# interface.net
KiCad netlist of a schematic drawn in Altium Designer
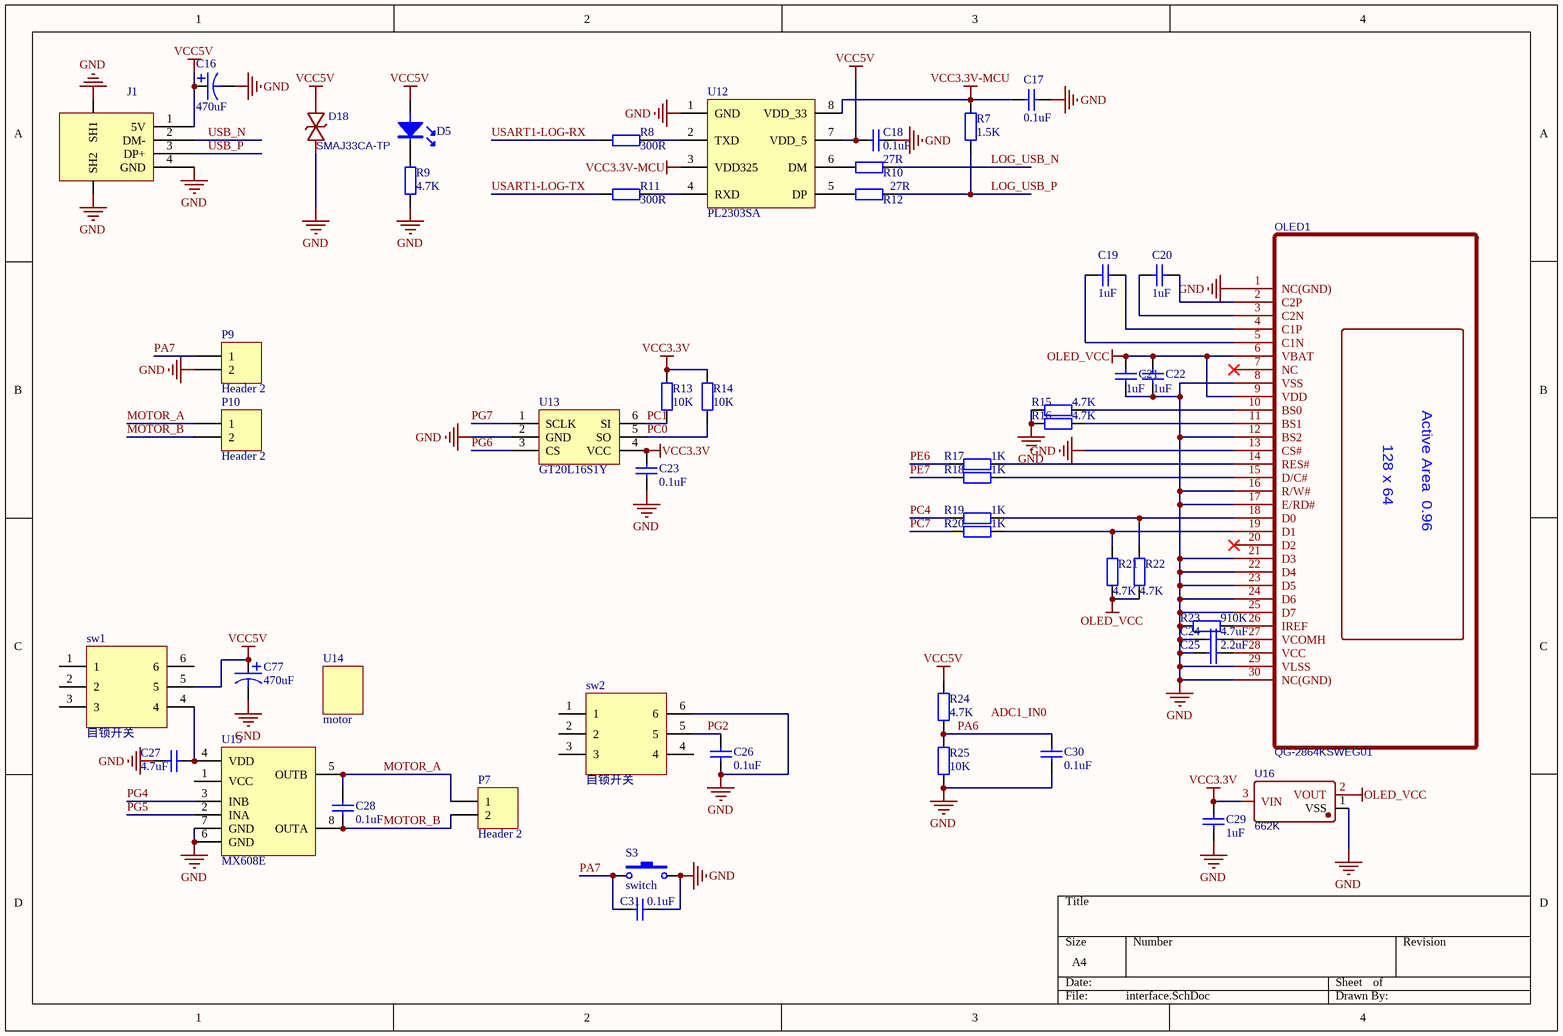
[diagram p0: interface.SchDoc]

(export (version "E")
  (design (tool "Eeschema 10.0.6"))
  (components
    (comp (ref "C16")
      (value "470uF")
      (footprint "CAP-SMD_BD10.0-L10.3-W10.3-FD")
      (description "贴片电容，1206")
      (libsource (lib "stm8l052r8t6开发板") (part "CAPACITOR"))
    )
    (comp (ref "C17")
      (value "0.1uF")
      (footprint "0603_C")
      (description "贴片电容，0603")
      (libsource (lib "extendBoard") (part "Cap"))
    )
    (comp (ref "C18")
      (value "0.1uF")
      (footprint "0603_C")
      (description "贴片电容，0603")
      (libsource (lib "extendBoard") (part "Cap"))
    )
    (comp (ref "C19")
      (value "1uF")
      (footprint "0603_C")
      (description "贴片电容，0603")
      (libsource (lib "stm8l052r8t6开发板") (part "Cap"))
    )
    (comp (ref "C20")
      (value "1uF")
      (footprint "0603_C")
      (description "贴片电容，0603")
      (libsource (lib "stm8l052r8t6开发板") (part "Cap"))
    )
    (comp (ref "C21")
      (value "1uF")
      (footprint "0603_C")
      (description "贴片电容，0603")
      (libsource (lib "stm8l052r8t6开发板") (part "Cap"))
    )
    (comp (ref "C22")
      (value "1uF")
      (footprint "0603_C")
      (description "贴片电容，0603")
      (libsource (lib "stm8l052r8t6开发板") (part "Cap"))
    )
    (comp (ref "C23")
      (value "0.1uF")
      (footprint "0603_C")
      (description "贴片电容，0603")
      (libsource (lib "stm8l052r8t6开发板") (part "Cap"))
    )
    (comp (ref "C24")
      (value "4.7uF")
      (footprint "0603_C")
      (description "贴片电容，0603")
      (libsource (lib "stm8l052r8t6开发板") (part "Cap"))
    )
    (comp (ref "C25")
      (value "2.2uF")
      (footprint "0603_C")
      (description "贴片电容，0603")
      (libsource (lib "stm8l052r8t6开发板") (part "Cap"))
    )
    (comp (ref "C26")
      (value "0.1uF")
      (footprint "0603_C")
      (description "贴片电容，0603")
      (libsource (lib "stm8l052r8t6开发板") (part "Cap"))
    )
    (comp (ref "C27")
      (value "4.7uF")
      (footprint "0603_C")
      (description "贴片电容，0603")
      (libsource (lib "extendBoard") (part "Cap"))
    )
    (comp (ref "C28")
      (value "0.1uF")
      (footprint "0603_C")
      (description "贴片电容，0603")
      (libsource (lib "extendBoard") (part "Cap"))
    )
    (comp (ref "C29")
      (value "1uF")
      (footprint "0603_C")
      (description "贴片电容，0603")
      (libsource (lib "stm8l052r8t6开发板") (part "Cap"))
    )
    (comp (ref "C30")
      (value "0.1uF")
      (footprint "0603_C")
      (description "贴片电容，0603")
      (libsource (lib "stm8l052r8t6开发板") (part "Cap"))
    )
    (comp (ref "C31")
      (value "0.1uF")
      (footprint "0603_C")
      (description "贴片电容，0603")
      (libsource (lib "stm8l052r8t6开发板") (part "Cap"))
    )
    (comp (ref "C77")
      (value "470uF")
      (footprint "CAP-SMD_BD10.0-L10.3-W10.3-FD")
      (description "贴片电容，1206")
      (libsource (lib "stm8l052r8t6开发板") (part "CAPACITOR"))
    )
    (comp (ref "D5")
      (value "LED")
      (footprint "0603_LED_S1")
      (description "贴片LED，0603，白色")
      (libsource (lib "stm8l052r8t6开发板") (part "LED"))
    )
    (comp (ref "D18")
      (value "SMAJ33CA-TP")
      (footprint "SMA_L4.4-W2.6-LS5.0-BI")
      (description "TVS")
      (libsource (lib "智能锁实践教学平台") (part "SMAJ33CA-TP"))
    )
    (comp (ref "J1")
      (value "USB接口")
      (footprint "USB_D")
      (description "USB-B10-BRW")
      (libsource (lib "stm8l052r8t6开发板") (part "USB"))
    )
    (comp (ref "OLED1")
      (value "QG-2864KSWEG01")
      (footprint "OLED-SMD_QG-2864KSWEG01-flod")
      (description "128x64 单色白色，QG-2864KSWEG01")
      (fields (field (name "BOM_SUPPLIER PART") "C85007"))
      (libsource (lib "stm8l052r8t6开发板") (part "QG-2864KSWEG01"))
    )
    (comp (ref "P7")
      (value "Header 2")
      (footprint "HDR1X2")
      (description "不焊")
      (fields (field (name "PUBLISHER") "Altium Limited"))
      (libsource (lib "Miscellaneous Connectors") (part "Header 2"))
    )
    (comp (ref "P9")
      (value "Header 2")
      (footprint "CONN-TH_WJ126V-5.0-2P")
      (description "WJ126V-5.0-2P，不焊")
      (libsource (lib "Miscellaneous Connectors") (part "Header 2"))
    )
    (comp (ref "P10")
      (value "Header 2")
      (footprint "CONN-TH_WJ126V-5.0-2P")
      (description "WJ126V-5.0-2P，不焊")
      (libsource (lib "Miscellaneous Connectors") (part "Header 2"))
    )
    (comp (ref "R7")
      (value "1.5K")
      (footprint "0603_R")
      (description "贴片电阻，0603")
      (libsource (lib "") (part "Res2_2"))
    )
    (comp (ref "R8")
      (value "300R")
      (footprint "0603_R")
      (description "贴片电阻，0603")
      (libsource (lib "") (part "Res2_1"))
    )
    (comp (ref "R9")
      (value "4.7K")
      (footprint "0603_R")
      (description "贴片电阻，0603")
      (libsource (lib "extendBoard") (part "Res2"))
    )
    (comp (ref "R10")
      (value "27R")
      (footprint "0603_R")
      (description "贴片电阻，0603")
      (libsource (lib "") (part "Res2_1"))
    )
    (comp (ref "R11")
      (value "300R")
      (footprint "0603_R")
      (description "贴片电阻，0603")
      (libsource (lib "") (part "Res2_1"))
    )
    (comp (ref "R12")
      (value "27R")
      (footprint "0603_R")
      (description "贴片电阻，0603")
      (libsource (lib "") (part "Res2_1"))
    )
    (comp (ref "R13")
      (value "10K")
      (footprint "0603_R")
      (description "贴片电阻，0603")
      (libsource (lib "stm8l052r8t6开发板") (part "Res2"))
    )
    (comp (ref "R14")
      (value "10K")
      (footprint "0603_R")
      (description "贴片电阻，0603")
      (libsource (lib "stm8l052r8t6开发板") (part "Res2"))
    )
    (comp (ref "R15")
      (value "4.7K")
      (footprint "0603_R")
      (description "贴片电阻，0603")
      (libsource (lib "") (part "Res2_1"))
    )
    (comp (ref "R16")
      (value "4.7K")
      (footprint "0603_R")
      (description "贴片电阻，0603")
      (libsource (lib "") (part "Res2_1"))
    )
    (comp (ref "R17")
      (value "1K")
      (footprint "0603_R")
      (description "贴片电阻，0603")
      (libsource (lib "") (part "Res2_1"))
    )
    (comp (ref "R18")
      (value "1K")
      (footprint "0603_R")
      (description "贴片电阻，0603")
      (libsource (lib "") (part "Res2_1"))
    )
    (comp (ref "R19")
      (value "1K")
      (footprint "0603_R")
      (description "贴片电阻，0603")
      (libsource (lib "") (part "Res2_1"))
    )
    (comp (ref "R20")
      (value "1K")
      (footprint "0603_R")
      (description "贴片电阻，0603")
      (libsource (lib "") (part "Res2_1"))
    )
    (comp (ref "R21")
      (value "4.7K")
      (footprint "0603_R")
      (description "贴片电阻，0603")
      (libsource (lib "stm8l052r8t6开发板") (part "Res2"))
    )
    (comp (ref "R22")
      (value "4.7K")
      (footprint "0603_R")
      (description "贴片电阻，0603")
      (libsource (lib "stm8l052r8t6开发板") (part "Res2"))
    )
    (comp (ref "R23")
      (value "910K")
      (footprint "0603_R")
      (description "贴片电阻，0603")
      (libsource (lib "") (part "Res2_2"))
    )
    (comp (ref "R24")
      (value "4.7K")
      (footprint "0603_R")
      (description "贴片电阻，0603")
      (libsource (lib "stm8l052r8t6开发板") (part "Res2"))
    )
    (comp (ref "R25")
      (value "10K")
      (footprint "0603_R")
      (description "贴片电阻，0603")
      (libsource (lib "stm8l052r8t6开发板") (part "Res2"))
    )
    (comp (ref "S3")
      (value "switch")
      (footprint "SW-SMD_4P-L6.2-W6.2-P4.50-LS9.0")
      (description "贴片按键，6*6*5")
      (libsource (lib "stm8l052r8t6开发板") (part "switch"))
    )
    (comp (ref "sw1")
      (value "自锁开关")
      (footprint "SW-TH_6P-L8.5-W8.5-P2.50-LS5.4-BL")
      (description "8.5*8.5*H22.35自锁按键开关")
      (libsource (lib "stm8l052r8t6开发板") (part "switch_lock"))
    )
    (comp (ref "sw2")
      (value "自锁开关")
      (footprint "SW-TH_6P-L8.5-W8.5-P2.50-LS5.4-BL")
      (description "8.5*8.5*H22.35自锁按键开关")
      (libsource (lib "stm8l052r8t6开发板") (part "switch_lock"))
    )
    (comp (ref "U12")
      (value "PL2303SA")
      (footprint "SOP-8_150mil")
      (description "USB转TTL芯片，PL2303SA，SOP-8_150mil")
      (libsource (lib "extendBoard") (part "PL2303SA"))
    )
    (comp (ref "U13")
      (value "GT20L16S1Y")
      (footprint "SOT-23-6")
      (description "字库芯片， SOT-23-6")
      (libsource (lib "stm8l052r8t6开发板") (part "GT20L16S1Y"))
    )
    (comp (ref "U14")
      (value "motor")
      (footprint "MH-JS030LK140")
      (description "顶呱呱工厂 MH-JS030LK140")
      (libsource (lib "stm8l052r8t6开发板") (part "motor"))
    )
    (comp (ref "U15")
      (value "MX608E")
      (footprint "SOP-8_150mil")
      (description "MX608E电机驱动，SOP8")
      (libsource (lib "stm8l052r8t6开发板") (part "MX608E"))
    )
    (comp (ref "U16")
      (value "662K")
      (footprint "SOT-23(SOT-23-3)")
      (description "线性稳压器662k,SOT23-3")
      (libsource (lib "stm8l052r8t6开发板") (part "662K"))
    )
  )
  (nets
    (net (code "2") (name "/LOG_USB_N") (class "Default")
      (node (ref "R10") (pin "2") (pinfunction "2_2") (pintype "passive"))
    )
    (net (code "3") (name "/LOG_USB_P") (class "Default")
      (node (ref "R12") (pin "2") (pinfunction "2_2") (pintype "passive"))
      (node (ref "R7") (pin "1") (pinfunction "1_1") (pintype "passive"))
    )
    (net (code "4") (name "/MOTOR_A") (class "Default")
      (node (ref "C28") (pin "1") (pinfunction "1_1") (pintype "passive"))
      (node (ref "P10") (pin "1") (pinfunction "1_1") (pintype "passive"))
      (node (ref "P7") (pin "1") (pinfunction "1_1") (pintype "passive"))
      (node (ref "U15") (pin "5") (pinfunction "OUTB_5") (pintype "passive"))
    )
    (net (code "5") (name "/MOTOR_B") (class "Default")
      (node (ref "C28") (pin "2") (pinfunction "2_2") (pintype "passive"))
      (node (ref "P10") (pin "2") (pinfunction "2_2") (pintype "passive"))
      (node (ref "P7") (pin "2") (pinfunction "2_2") (pintype "passive"))
      (node (ref "U15") (pin "8") (pinfunction "OUTA_8") (pintype "passive"))
    )
    (net (code "6") (name "/PA6") (class "Default")
      (node (ref "C30") (pin "2") (pinfunction "2_2") (pintype "passive"))
      (node (ref "R24") (pin "1") (pinfunction "1_1") (pintype "passive"))
      (node (ref "R25") (pin "2") (pinfunction "2_2") (pintype "passive"))
    )
    (net (code "7") (name "/PA7") (class "Default")
      (node (ref "C31") (pin "1") (pinfunction "1_1") (pintype "passive"))
      (node (ref "P9") (pin "1") (pinfunction "1_1") (pintype "passive"))
      (node (ref "S3") (pin "1") (pinfunction "1_1") (pintype "passive"))
    )
    (net (code "8") (name "/PC0") (class "Default")
      (node (ref "R14") (pin "1") (pinfunction "1_1") (pintype "passive"))
      (node (ref "U13") (pin "5") (pinfunction "SO_5") (pintype "passive"))
    )
    (net (code "9") (name "/PC1") (class "Default")
      (node (ref "R13") (pin "1") (pinfunction "1_1") (pintype "passive"))
      (node (ref "U13") (pin "6") (pinfunction "SI_6") (pintype "passive"))
    )
    (net (code "10") (name "/PC4") (class "Default")
      (node (ref "R19") (pin "1") (pinfunction "1_1") (pintype "passive"))
    )
    (net (code "11") (name "/PC7") (class "Default")
      (node (ref "R20") (pin "1") (pinfunction "1_1") (pintype "passive"))
    )
    (net (code "12") (name "/PE6") (class "Default")
      (node (ref "R17") (pin "1") (pinfunction "1_1") (pintype "passive"))
    )
    (net (code "13") (name "/PE7") (class "Default")
      (node (ref "R18") (pin "1") (pinfunction "1_1") (pintype "passive"))
    )
    (net (code "14") (name "/PG2") (class "Default")
      (node (ref "C26") (pin "2") (pinfunction "2_2") (pintype "passive"))
      (node (ref "sw2") (pin "5") (pinfunction "5_5") (pintype "passive"))
    )
    (net (code "15") (name "/PG4") (class "Default")
      (node (ref "U15") (pin "3") (pinfunction "INB_3") (pintype "passive"))
    )
    (net (code "16") (name "/PG5") (class "Default")
      (node (ref "U15") (pin "2") (pinfunction "INA_2") (pintype "passive"))
    )
    (net (code "17") (name "/PG6") (class "Default")
      (node (ref "U13") (pin "3") (pinfunction "CS_3") (pintype "passive"))
    )
    (net (code "18") (name "/PG7") (class "Default")
      (node (ref "U13") (pin "1") (pinfunction "SCLK_1") (pintype "passive"))
    )
    (net (code "19") (name "/USART1-LOG-RX") (class "Default")
      (node (ref "R8") (pin "1") (pinfunction "1_1") (pintype "passive"))
    )
    (net (code "20") (name "/USART1-LOG-TX") (class "Default")
      (node (ref "R11") (pin "1") (pinfunction "1_1") (pintype "passive"))
    )
    (net (code "21") (name "/USB_N") (class "Default")
      (node (ref "J1") (pin "2") (pinfunction "DM-_2") (pintype "passive"))
    )
    (net (code "22") (name "/USB_P") (class "Default")
      (node (ref "J1") (pin "3") (pinfunction "DP+_3") (pintype "passive"))
    )
    (net (code "23") (name "GND") (class "Default")
      (node (ref "C16") (pin "2") (pinfunction "2_2") (pintype "passive"))
      (node (ref "C17") (pin "1") (pinfunction "1_1") (pintype "passive"))
      (node (ref "C18") (pin "2") (pinfunction "2_2") (pintype "passive"))
      (node (ref "C21") (pin "2") (pinfunction "2_2") (pintype "passive"))
      (node (ref "C22") (pin "2") (pinfunction "2_2") (pintype "passive"))
      (node (ref "C23") (pin "1") (pinfunction "1_1") (pintype "passive"))
      (node (ref "C24") (pin "1") (pinfunction "1_1") (pintype "passive"))
      (node (ref "C25") (pin "1") (pinfunction "1_1") (pintype "passive"))
      (node (ref "C26") (pin "1") (pinfunction "1_1") (pintype "passive"))
      (node (ref "C27") (pin "1") (pinfunction "1_1") (pintype "passive"))
      (node (ref "C29") (pin "2") (pinfunction "2_2") (pintype "passive"))
      (node (ref "C30") (pin "1") (pinfunction "1_1") (pintype "passive"))
      (node (ref "C31") (pin "2") (pinfunction "2_2") (pintype "passive"))
      (node (ref "C77") (pin "2") (pinfunction "2_2") (pintype "passive"))
      (node (ref "D18") (pin "1") (pinfunction "1_1") (pintype "passive"))
      (node (ref "J1") (pin "4") (pinfunction "GND_4") (pintype "passive"))
      (node (ref "J1") (pin "SH1") (pinfunction "SH1_SH1") (pintype "passive"))
      (node (ref "J1") (pin "SH2") (pinfunction "SH2_SH2") (pintype "passive"))
      (node (ref "OLED1") (pin "1") (pinfunction "NC(GND)_1") (pintype "passive"))
      (node (ref "OLED1") (pin "12") (pinfunction "BS2_12") (pintype "passive"))
      (node (ref "OLED1") (pin "13") (pinfunction "CS#_13") (pintype "passive"))
      (node (ref "OLED1") (pin "16") (pinfunction "R/W#_16") (pintype "passive"))
      (node (ref "OLED1") (pin "17") (pinfunction "E/RD#_17") (pintype "passive"))
      (node (ref "OLED1") (pin "21") (pinfunction "D3_21") (pintype "passive"))
      (node (ref "OLED1") (pin "22") (pinfunction "D4_22") (pintype "passive"))
      (node (ref "OLED1") (pin "23") (pinfunction "D5_23") (pintype "passive"))
      (node (ref "OLED1") (pin "24") (pinfunction "D6_24") (pintype "passive"))
      (node (ref "OLED1") (pin "25") (pinfunction "D7_25") (pintype "passive"))
      (node (ref "OLED1") (pin "29") (pinfunction "VLSS_29") (pintype "passive"))
      (node (ref "OLED1") (pin "30") (pinfunction "NC(GND)_30") (pintype "passive"))
      (node (ref "OLED1") (pin "8") (pinfunction "VSS_8") (pintype "passive"))
      (node (ref "P9") (pin "2") (pinfunction "2_2") (pintype "passive"))
      (node (ref "R15") (pin "1") (pinfunction "1_1") (pintype "passive"))
      (node (ref "R16") (pin "1") (pinfunction "1_1") (pintype "passive"))
      (node (ref "R23") (pin "2") (pinfunction "2_2") (pintype "passive"))
      (node (ref "R25") (pin "1") (pinfunction "1_1") (pintype "passive"))
      (node (ref "R9") (pin "2") (pinfunction "2_2") (pintype "passive"))
      (node (ref "S3") (pin "2") (pinfunction "2_2") (pintype "passive"))
      (node (ref "U12") (pin "1") (pinfunction "GND_1") (pintype "passive"))
      (node (ref "U13") (pin "2") (pinfunction "GND_2") (pintype "passive"))
      (node (ref "U15") (pin "6") (pinfunction "GND_6") (pintype "passive"))
      (node (ref "U15") (pin "7") (pinfunction "GND_7") (pintype "passive"))
      (node (ref "U16") (pin "1") (pinfunction "VSS_1") (pintype "passive"))
      (node (ref "sw2") (pin "6") (pinfunction "6_6") (pintype "passive"))
    )
    (net (code "24") (name "Net-(D5-PadK)") (class "Default")
      (node (ref "D5") (pin "K") (pinfunction "K_K") (pintype "passive"))
      (node (ref "R9") (pin "1") (pinfunction "1_1") (pintype "passive"))
    )
    (net (code "25") (name "Net-(OLED1-BS0)") (class "Default")
      (node (ref "OLED1") (pin "10") (pinfunction "BS0_10") (pintype "passive"))
      (node (ref "R15") (pin "2") (pinfunction "2_2") (pintype "passive"))
    )
    (net (code "26") (name "Net-(OLED1-BS1)") (class "Default")
      (node (ref "OLED1") (pin "11") (pinfunction "BS1_11") (pintype "passive"))
      (node (ref "R16") (pin "2") (pinfunction "2_2") (pintype "passive"))
    )
    (net (code "27") (name "Net-(OLED1-C1N)") (class "Default")
      (node (ref "C19") (pin "2") (pinfunction "2_2") (pintype "passive"))
      (node (ref "OLED1") (pin "5") (pinfunction "C1N_5") (pintype "passive"))
    )
    (net (code "28") (name "Net-(OLED1-C1P)") (class "Default")
      (node (ref "C19") (pin "1") (pinfunction "1_1") (pintype "passive"))
      (node (ref "OLED1") (pin "4") (pinfunction "C1P_4") (pintype "passive"))
    )
    (net (code "29") (name "Net-(OLED1-C2N)") (class "Default")
      (node (ref "C20") (pin "2") (pinfunction "2_2") (pintype "passive"))
      (node (ref "OLED1") (pin "3") (pinfunction "C2N_3") (pintype "passive"))
    )
    (net (code "30") (name "Net-(OLED1-C2P)") (class "Default")
      (node (ref "C20") (pin "1") (pinfunction "1_1") (pintype "passive"))
      (node (ref "OLED1") (pin "2") (pinfunction "C2P_2") (pintype "passive"))
    )
    (net (code "31") (name "Net-(OLED1-D0)") (class "Default")
      (node (ref "OLED1") (pin "18") (pinfunction "D0_18") (pintype "passive"))
      (node (ref "R19") (pin "2") (pinfunction "2_2") (pintype "passive"))
      (node (ref "R22") (pin "2") (pinfunction "2_2") (pintype "passive"))
    )
    (net (code "32") (name "Net-(OLED1-D1)") (class "Default")
      (node (ref "OLED1") (pin "19") (pinfunction "D1_19") (pintype "passive"))
      (node (ref "R20") (pin "2") (pinfunction "2_2") (pintype "passive"))
      (node (ref "R21") (pin "2") (pinfunction "2_2") (pintype "passive"))
    )
    (net (code "33") (name "Net-(OLED1-D{slash}C#)") (class "Default")
      (node (ref "OLED1") (pin "15") (pinfunction "D/C#_15") (pintype "passive"))
      (node (ref "R18") (pin "2") (pinfunction "2_2") (pintype "passive"))
    )
    (net (code "34") (name "Net-(OLED1-IREF)") (class "Default")
      (node (ref "OLED1") (pin "26") (pinfunction "IREF_26") (pintype "passive"))
      (node (ref "R23") (pin "1") (pinfunction "1_1") (pintype "passive"))
    )
    (net (code "35") (name "Net-(OLED1-RES#)") (class "Default")
      (node (ref "OLED1") (pin "14") (pinfunction "RES#_14") (pintype "passive"))
      (node (ref "R17") (pin "2") (pinfunction "2_2") (pintype "passive"))
    )
    (net (code "36") (name "Net-(OLED1-VCC)") (class "Default")
      (node (ref "C25") (pin "2") (pinfunction "2_2") (pintype "passive"))
      (node (ref "OLED1") (pin "28") (pinfunction "VCC_28") (pintype "passive"))
    )
    (net (code "37") (name "Net-(OLED1-VCOMH)") (class "Default")
      (node (ref "C24") (pin "2") (pinfunction "2_2") (pintype "passive"))
      (node (ref "OLED1") (pin "27") (pinfunction "VCOMH_27") (pintype "passive"))
    )
    (net (code "38") (name "Net-(U12-DM)") (class "Default")
      (node (ref "R10") (pin "1") (pinfunction "1_1") (pintype "passive"))
      (node (ref "U12") (pin "6") (pinfunction "DM_6") (pintype "passive"))
    )
    (net (code "39") (name "Net-(U12-DP)") (class "Default")
      (node (ref "R12") (pin "1") (pinfunction "1_1") (pintype "passive"))
      (node (ref "U12") (pin "5") (pinfunction "DP_5") (pintype "passive"))
    )
    (net (code "40") (name "Net-(U12-RXD)") (class "Default")
      (node (ref "R11") (pin "2") (pinfunction "2_2") (pintype "passive"))
      (node (ref "U12") (pin "4") (pinfunction "RXD_4") (pintype "passive"))
    )
    (net (code "41") (name "Net-(U12-TXD)") (class "Default")
      (node (ref "R8") (pin "2") (pinfunction "2_2") (pintype "passive"))
      (node (ref "U12") (pin "2") (pinfunction "TXD_2") (pintype "passive"))
    )
    (net (code "42") (name "Net-(U15-VDD)") (class "Default")
      (node (ref "C27") (pin "2") (pinfunction "2_2") (pintype "passive"))
      (node (ref "U15") (pin "4") (pinfunction "VDD_4") (pintype "passive"))
      (node (ref "sw1") (pin "4") (pinfunction "4_4") (pintype "passive"))
    )
    (net (code "43") (name "OLED_VCC") (class "Default")
      (node (ref "C21") (pin "1") (pinfunction "1_1") (pintype "passive"))
      (node (ref "C22") (pin "1") (pinfunction "1_1") (pintype "passive"))
      (node (ref "OLED1") (pin "6") (pinfunction "VBAT_6") (pintype "passive"))
      (node (ref "OLED1") (pin "9") (pinfunction "VDD_9") (pintype "passive"))
      (node (ref "R21") (pin "1") (pinfunction "1_1") (pintype "passive"))
      (node (ref "R22") (pin "1") (pinfunction "1_1") (pintype "passive"))
      (node (ref "U16") (pin "2") (pinfunction "VOUT_2") (pintype "passive"))
    )
    (net (code "44") (name "VCC3.3V") (class "Default")
      (node (ref "C23") (pin "2") (pinfunction "2_2") (pintype "passive"))
      (node (ref "C29") (pin "1") (pinfunction "1_1") (pintype "passive"))
      (node (ref "R13") (pin "2") (pinfunction "2_2") (pintype "passive"))
      (node (ref "R14") (pin "2") (pinfunction "2_2") (pintype "passive"))
      (node (ref "U13") (pin "4") (pinfunction "VCC_4") (pintype "passive"))
      (node (ref "U16") (pin "3") (pinfunction "VIN_3") (pintype "passive"))
    )
    (net (code "45") (name "VCC3.3V-MCU") (class "Default")
      (node (ref "C17") (pin "2") (pinfunction "2_2") (pintype "passive"))
      (node (ref "R7") (pin "2") (pinfunction "2_2") (pintype "passive"))
      (node (ref "U12") (pin "3") (pinfunction "VDD325_3") (pintype "passive"))
      (node (ref "U12") (pin "8") (pinfunction "VDD_33_8") (pintype "passive"))
    )
    (net (code "46") (name "VCC5V") (class "Default")
      (node (ref "C16") (pin "1") (pinfunction "1_1") (pintype "passive"))
      (node (ref "C18") (pin "1") (pinfunction "1_1") (pintype "passive"))
      (node (ref "C77") (pin "1") (pinfunction "1_1") (pintype "passive"))
      (node (ref "D18") (pin "2") (pinfunction "2_2") (pintype "passive"))
      (node (ref "D5") (pin "A") (pinfunction "A_A") (pintype "passive"))
      (node (ref "J1") (pin "1") (pinfunction "5V_1") (pintype "passive"))
      (node (ref "R24") (pin "2") (pinfunction "2_2") (pintype "passive"))
      (node (ref "U12") (pin "7") (pinfunction "VDD_5_7") (pintype "passive"))
      (node (ref "sw1") (pin "5") (pinfunction "5_5") (pintype "passive"))
    )
    (net (code "47") (name "unconnected-(OLED1-D2-Pad20)") (class "Default")
      (node (ref "OLED1") (pin "20") (pinfunction "D2_20") (pintype "passive+no_connect"))
    )
    (net (code "48") (name "unconnected-(OLED1-NC-Pad7)") (class "Default")
      (node (ref "OLED1") (pin "7") (pinfunction "NC_7") (pintype "passive+no_connect"))
    )
    (net (code "49") (name "unconnected-(U15-VCC-Pad1)") (class "Default")
      (node (ref "U15") (pin "1") (pinfunction "VCC_1") (pintype "passive"))
    )
    (net (code "50") (name "unconnected-(sw1-Pad1)") (class "Default")
      (node (ref "sw1") (pin "1") (pinfunction "1_1") (pintype "passive"))
    )
    (net (code "51") (name "unconnected-(sw1-Pad2)") (class "Default")
      (node (ref "sw1") (pin "2") (pinfunction "2_2") (pintype "passive"))
    )
    (net (code "52") (name "unconnected-(sw1-Pad3)") (class "Default")
      (node (ref "sw1") (pin "3") (pinfunction "3_3") (pintype "passive"))
    )
    (net (code "53") (name "unconnected-(sw1-Pad6)") (class "Default")
      (node (ref "sw1") (pin "6") (pinfunction "6_6") (pintype "passive"))
    )
    (net (code "54") (name "unconnected-(sw2-Pad1)") (class "Default")
      (node (ref "sw2") (pin "1") (pinfunction "1_1") (pintype "passive"))
    )
    (net (code "55") (name "unconnected-(sw2-Pad2)") (class "Default")
      (node (ref "sw2") (pin "2") (pinfunction "2_2") (pintype "passive"))
    )
    (net (code "56") (name "unconnected-(sw2-Pad3)") (class "Default")
      (node (ref "sw2") (pin "3") (pinfunction "3_3") (pintype "passive"))
    )
    (net (code "57") (name "unconnected-(sw2-Pad4)") (class "Default")
      (node (ref "sw2") (pin "4") (pinfunction "4_4") (pintype "passive"))
    )
  )
)
